# Water_level_schematic.net
KiCad netlist of a schematic drawn in EAGLE
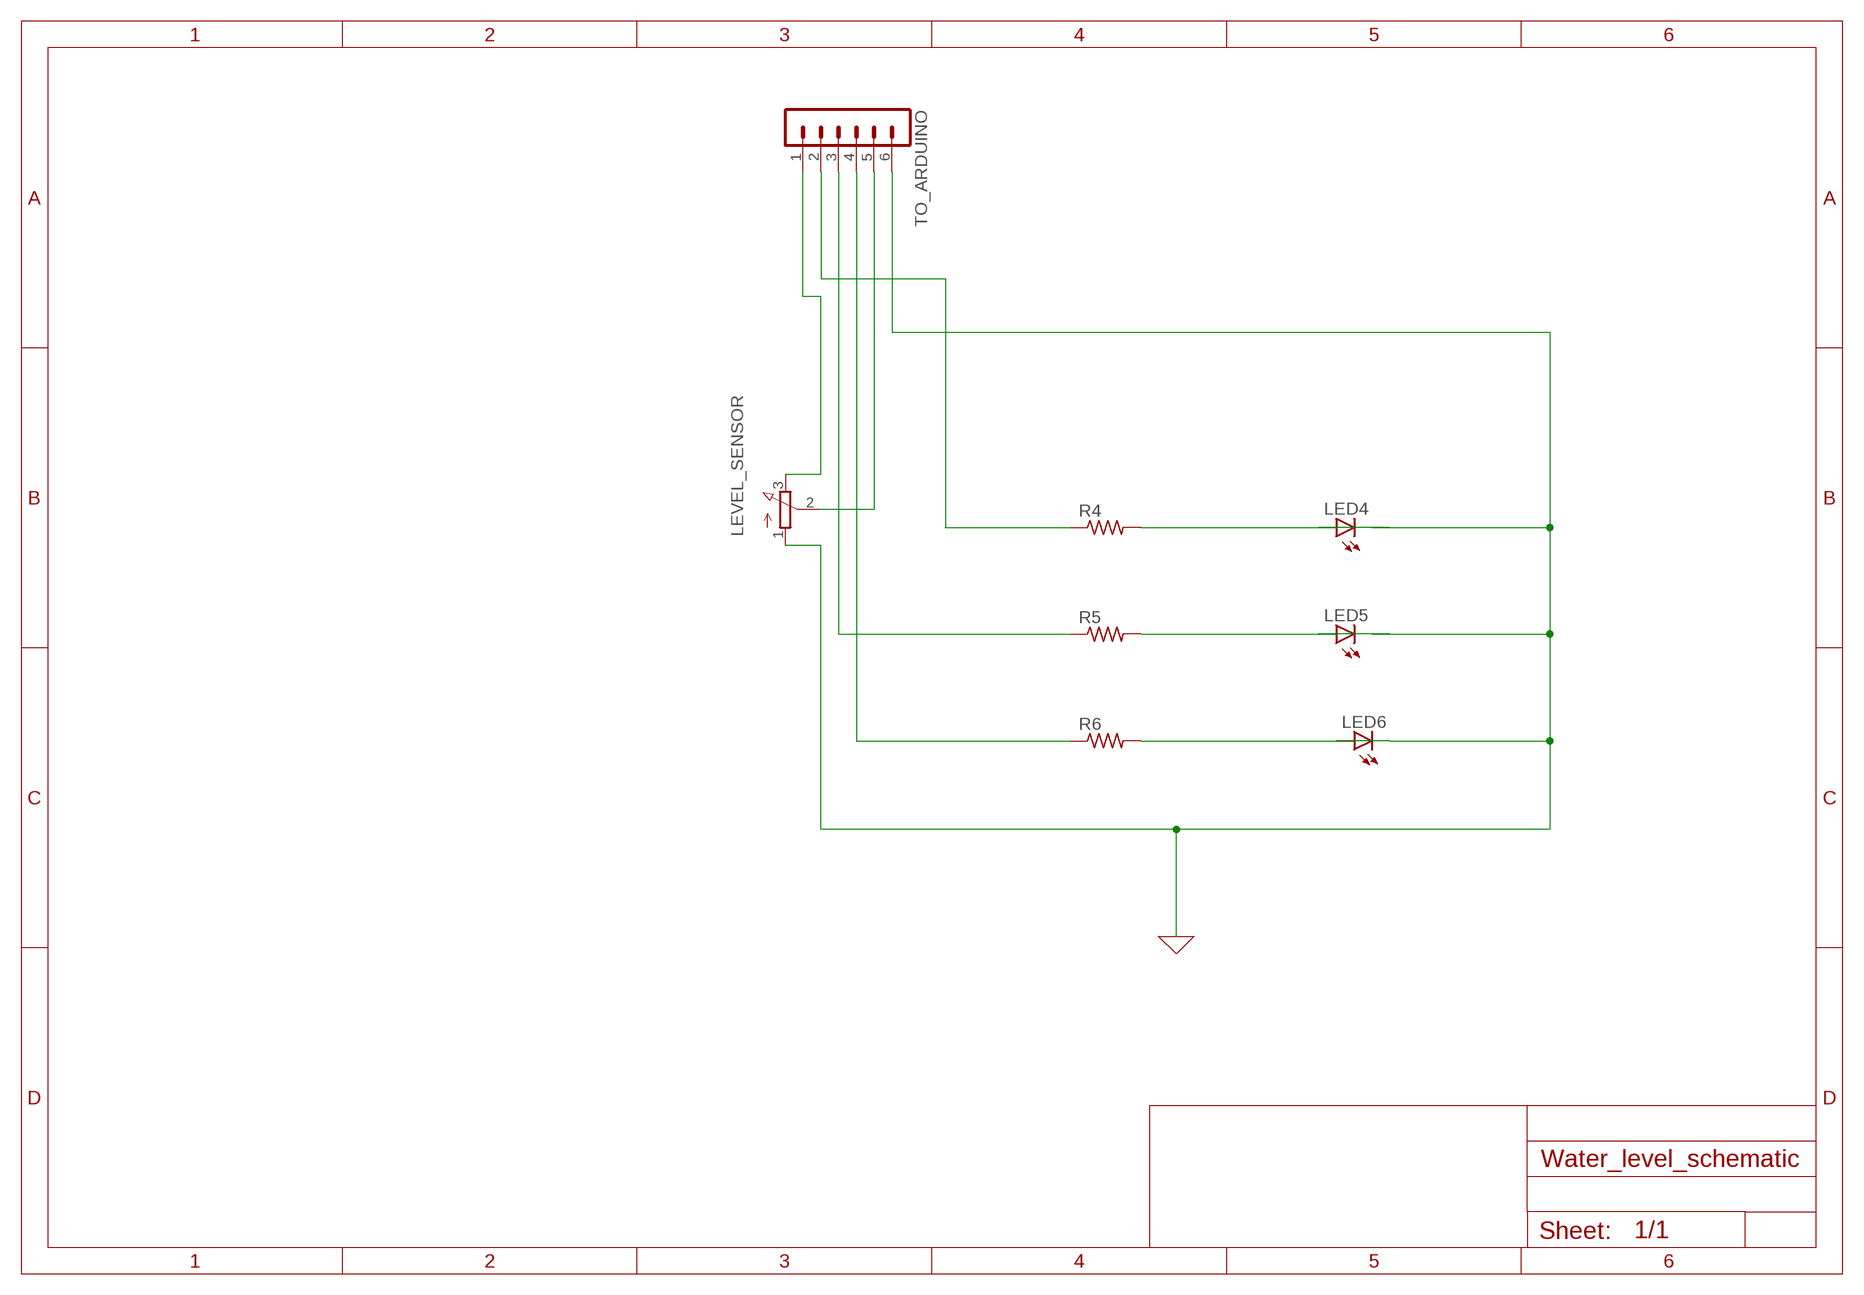
[diagram p0: schematic, sheet 1]

(export (version "E")
  (design (tool "Eeschema 10.0.6"))
  (components
    (comp (ref "LED4")
      (value "LED5MM")
      (footprint "eagle-import:LED5MM")
      (libsource (lib "eagle-import") (part "LED5MM"))
    )
    (comp (ref "LED5")
      (value "LED5MM")
      (footprint "eagle-import:LED5MM")
      (libsource (lib "eagle-import") (part "LED5MM"))
    )
    (comp (ref "LED6")
      (value "LED5MM")
      (footprint "eagle-import:LED5MM")
      (libsource (lib "eagle-import") (part "LED5MM"))
    )
    (comp (ref "LEVEL_SENSOR")
      (value "3RP/1610N")
      (footprint "eagle-import:3RP_1610N")
      (libsource (lib "eagle-import") (part "3RP/1610N"))
    )
    (comp (ref "R4")
      (value "R-US_0204/7")
      (footprint "eagle-import:0204_7")
      (libsource (lib "eagle-import") (part "R-US_0204/7"))
    )
    (comp (ref "R5")
      (value "R-US_0204/7")
      (footprint "eagle-import:0204_7")
      (libsource (lib "eagle-import") (part "R-US_0204/7"))
    )
    (comp (ref "R6")
      (value "R-US_0204/7")
      (footprint "eagle-import:0204_7")
      (libsource (lib "eagle-import") (part "R-US_0204/7"))
    )
    (comp (ref "TO_ARDUINO")
      (value "MA06-1")
      (footprint "eagle-import:MA06-1")
      (libsource (lib "eagle-import") (part "MA06-1"))
    )
  )
  (nets
    (net (code "1") (name "GND") (class "Default")
      (node (ref "LED4") (pin "K") (pinfunction "C_K") (pintype "passive"))
      (node (ref "LED5") (pin "K") (pinfunction "C_K") (pintype "passive"))
      (node (ref "LED6") (pin "A") (pinfunction "A_A") (pintype "passive"))
      (node (ref "LED6") (pin "K") (pinfunction "C_K") (pintype "passive"))
      (node (ref "LEVEL_SENSOR") (pin "1") (pinfunction "A_1") (pintype "passive"))
      (node (ref "R6") (pin "2") (pinfunction "2_2") (pintype "passive"))
      (node (ref "TO_ARDUINO") (pin "6") (pinfunction "6_6") (pintype "passive"))
    )
    (net (code "2") (name "Net-(LEVEL_SENSOR-E)") (class "Default")
      (node (ref "LEVEL_SENSOR") (pin "3") (pinfunction "E_3") (pintype "passive"))
      (node (ref "TO_ARDUINO") (pin "1") (pinfunction "1_1") (pintype "passive"))
    )
    (net (code "3") (name "Net-(LEVEL_SENSOR-S)") (class "Default")
      (node (ref "LEVEL_SENSOR") (pin "2") (pinfunction "S_2") (pintype "passive"))
      (node (ref "TO_ARDUINO") (pin "5") (pinfunction "5_5") (pintype "passive"))
    )
    (net (code "4") (name "Net-(R4-Pad1)") (class "Default")
      (node (ref "R4") (pin "1") (pinfunction "1_1") (pintype "passive"))
      (node (ref "TO_ARDUINO") (pin "2") (pinfunction "2_2") (pintype "passive"))
    )
    (net (code "5") (name "Net-(R5-Pad1)") (class "Default")
      (node (ref "R5") (pin "1") (pinfunction "1_1") (pintype "passive"))
      (node (ref "TO_ARDUINO") (pin "3") (pinfunction "3_3") (pintype "passive"))
    )
    (net (code "6") (name "Net-(R6-Pad1)") (class "Default")
      (node (ref "R6") (pin "1") (pinfunction "1_1") (pintype "passive"))
      (node (ref "TO_ARDUINO") (pin "4") (pinfunction "4_4") (pintype "passive"))
    )
    (net (code "7") (name "unconnected-(LED4-PadA)") (class "Default")
      (node (ref "LED4") (pin "A") (pinfunction "A_A") (pintype "passive"))
    )
    (net (code "8") (name "unconnected-(LED5-PadA)") (class "Default")
      (node (ref "LED5") (pin "A") (pinfunction "A_A") (pintype "passive"))
    )
    (net (code "9") (name "unconnected-(R4-Pad2)") (class "Default")
      (node (ref "R4") (pin "2") (pinfunction "2_2") (pintype "passive"))
    )
    (net (code "10") (name "unconnected-(R5-Pad2)") (class "Default")
      (node (ref "R5") (pin "2") (pinfunction "2_2") (pintype "passive"))
    )
  )
)
